# ST_LINK_V2_1.net
KiCad netlist of a schematic drawn in Altium Designer
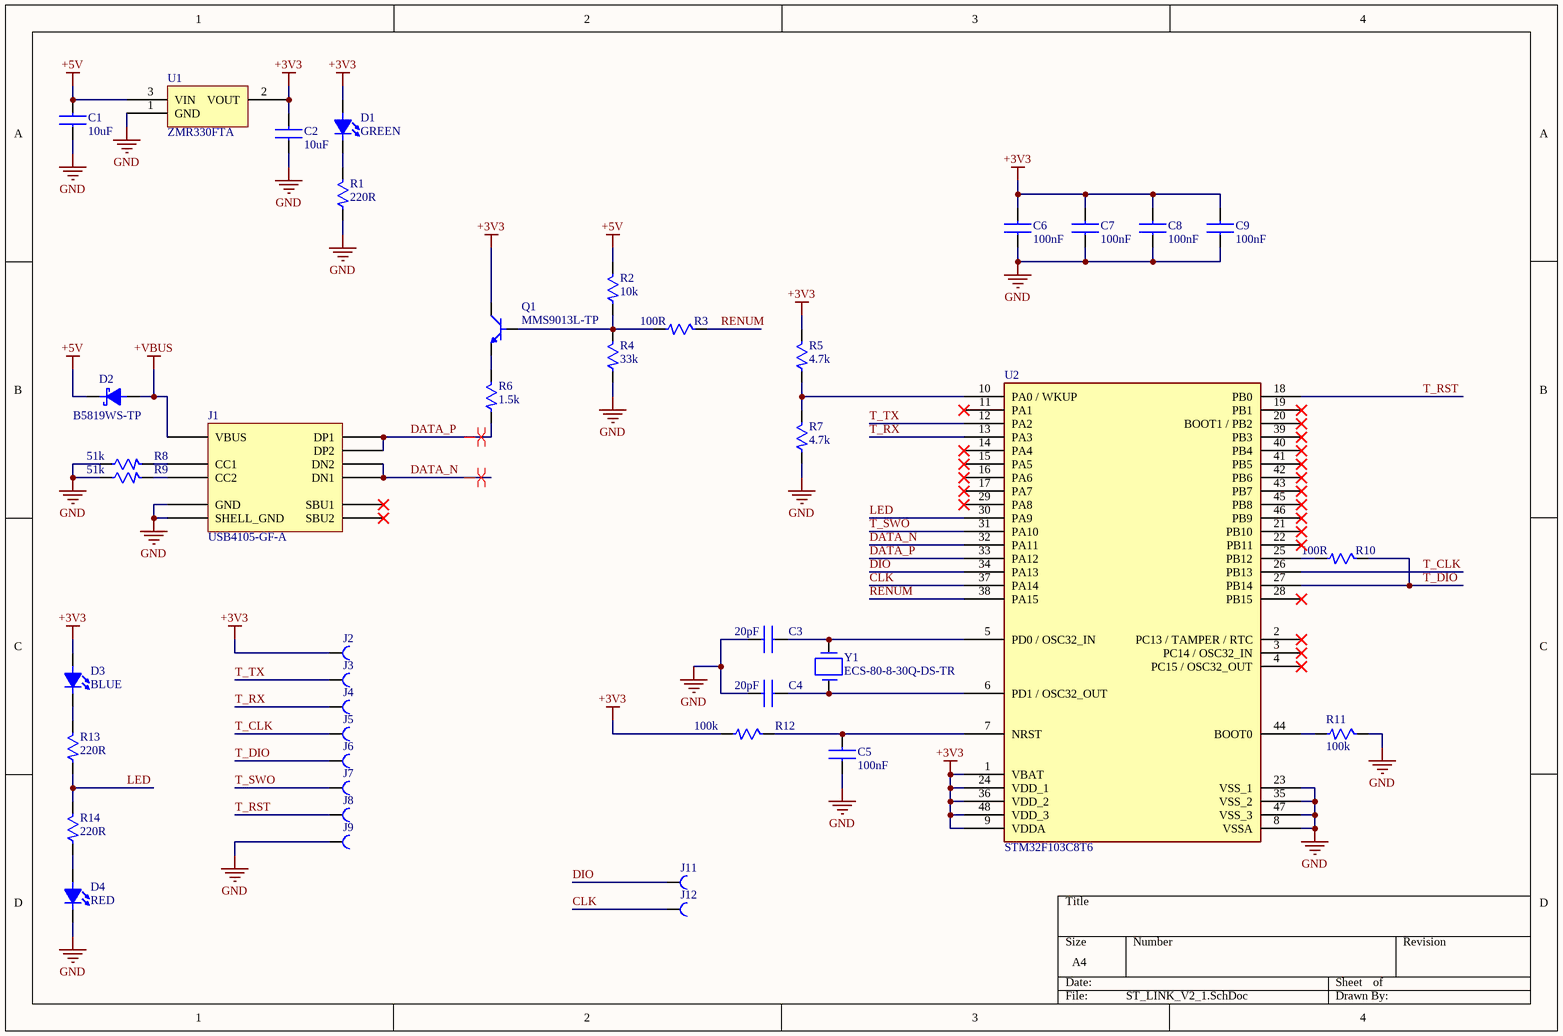
[diagram p0: ST_LINK_V2_1.SchDoc]

(export (version "E")
  (design (tool "Eeschema 10.0.6"))
  (components
    (comp (ref "C1")
      (value "10uF")
      (footprint "C_0603")
      (description "C Series 0603 10 uF 6.3 V ±10 % Tolerance X5R SMT Multilayer Ceramic Capacitor")
      (fields
        (field (name "MANUFACTURER") "TDK")
        (field (name "MANUFACTURER PART NUMBER") "C1608X5R0J106K080AB")
      )
      (libsource (lib "Altium_Library") (part "C1608X5R0J106K080AB"))
    )
    (comp (ref "C2")
      (value "10uF")
      (footprint "C_0603")
      (description "C Series 0603 10 uF 6.3 V ±10 % Tolerance X5R SMT Multilayer Ceramic Capacitor")
      (fields
        (field (name "MANUFACTURER") "TDK")
        (field (name "MANUFACTURER PART NUMBER") "C1608X5R0J106K080AB")
      )
      (libsource (lib "Altium_Library") (part "C1608X5R0J106K080AB"))
    )
    (comp (ref "C3")
      (value "20pF")
      (footprint "C_0603")
      (description "Cap Cer 0603 20PF 16V Ultra Stab")
      (fields
        (field (name "MANUFACTURER") "KEMET")
        (field (name "MANUFACTURER PART NUMBER") "C0603C200K4HACAUTO")
      )
      (libsource (lib "Altium_Library") (part "C0603C200K4HACAUTO"))
    )
    (comp (ref "C4")
      (value "20pF")
      (footprint "C_0603")
      (description "Cap Cer 0603 20PF 16V Ultra Stab")
      (fields
        (field (name "MANUFACTURER") "KEMET")
        (field (name "MANUFACTURER PART NUMBER") "C0603C200K4HACAUTO")
      )
      (libsource (lib "Altium_Library") (part "C0603C200K4HACAUTO"))
    )
    (comp (ref "C5")
      (value "100nF")
      (footprint "C_0603")
      (description "Cap Ceramic 0.1uF 16V X7R 20% SMD 0603 125 Paper T/R")
      (fields
        (field (name "MANUFACTURER") "KEMET")
        (field (name "MANUFACTURER PART NUMBER") "C0603C104M4RAC7411")
      )
      (libsource (lib "Altium_Library") (part "C0603C104M4RAC7411"))
    )
    (comp (ref "C6")
      (value "100nF")
      (footprint "C_0603")
      (description "Cap Ceramic 0.1uF 16V X7R 20% SMD 0603 125 Paper T/R")
      (fields
        (field (name "MANUFACTURER") "KEMET")
        (field (name "MANUFACTURER PART NUMBER") "C0603C104M4RAC7411")
      )
      (libsource (lib "Altium_Library") (part "C0603C104M4RAC7411"))
    )
    (comp (ref "C7")
      (value "100nF")
      (footprint "C_0603")
      (description "Cap Ceramic 0.1uF 16V X7R 20% SMD 0603 125 Paper T/R")
      (fields
        (field (name "MANUFACTURER") "KEMET")
        (field (name "MANUFACTURER PART NUMBER") "C0603C104M4RAC7411")
      )
      (libsource (lib "Altium_Library") (part "C0603C104M4RAC7411"))
    )
    (comp (ref "C8")
      (value "100nF")
      (footprint "C_0603")
      (description "Cap Ceramic 0.1uF 16V X7R 20% SMD 0603 125 Paper T/R")
      (fields
        (field (name "MANUFACTURER") "KEMET")
        (field (name "MANUFACTURER PART NUMBER") "C0603C104M4RAC7411")
      )
      (libsource (lib "Altium_Library") (part "C0603C104M4RAC7411"))
    )
    (comp (ref "C9")
      (value "100nF")
      (footprint "C_0603")
      (description "Cap Ceramic 0.1uF 16V X7R 20% SMD 0603 125 Paper T/R")
      (fields
        (field (name "MANUFACTURER") "KEMET")
        (field (name "MANUFACTURER PART NUMBER") "C0603C104M4RAC7411")
      )
      (libsource (lib "Altium_Library") (part "C0603C104M4RAC7411"))
    )
    (comp (ref "D1")
      (value "GREEN")
      (footprint "LED_0603_G")
      (description "Led, Green, 520 Nm, 3.2 V, 30 Ma, 430 Mcd Rohs Compliant: Yes")
      (fields
        (field (name "MANUFACTURER") "Wurth Electronics")
        (field (name "MANUFACTURER PART NUMBER") "150060GS75000")
      )
      (libsource (lib "Altium_Library") (part "150060GS75000"))
    )
    (comp (ref "D2")
      (value "B5819WS-TP")
      (footprint "SOD_323")
      (description "DIODE SCHOTTKY 40V 1A SOD323")
      (fields (field (name "MANUFACTURER") "MCC"))
      (libsource (lib "Altium_Library") (part "B5819WS-TP"))
    )
    (comp (ref "D3")
      (value "BLUE")
      (footprint "LED_0603_B")
      (description "SMT Mono-color Chip Led Watercle")
      (fields
        (field (name "MANUFACTURER") "Wurth Electronics")
        (field (name "MANUFACTURER PART NUMBER") "150060BS75003")
      )
      (libsource (lib "Altium_Library") (part "150060BS75003"))
    )
    (comp (ref "D4")
      (value "RED")
      (footprint "LED_0603_R")
      (description "LED Low-Power Uni-Color Red 630nm 2V 2-Pin Chip 0603(1608Metric) T/R")
      (fields
        (field (name "MANUFACTURER") "Wurth Electronics")
        (field (name "MANUFACTURER PART NUMBER") "150060RS75000")
      )
      (libsource (lib "Altium_Library") (part "150060RS75000"))
    )
    (comp (ref "J1")
      (value "USB4105-GF-A")
      (footprint "USB4105-GF-A")
      (description "Conn USB 2.0 Type C RCP 24 POS 0.3mm/0.5mm Solder RA SMD 24 Terminal 1 Port T/R")
      (fields (field (name "MANUFACTURER") "Global Connector Technology"))
      (libsource (lib "Altium_Library") (part "USB4105-GF-A"))
    )
    (comp (ref "J2")
      (value "CONST_PAD")
      (footprint "CONST_PAD")
      (libsource (lib "Altium_Library") (part "CONST_PAD"))
    )
    (comp (ref "J3")
      (value "CONST_PAD")
      (footprint "CONST_PAD")
      (libsource (lib "Altium_Library") (part "CONST_PAD"))
    )
    (comp (ref "J4")
      (value "CONST_PAD")
      (footprint "CONST_PAD")
      (libsource (lib "Altium_Library") (part "CONST_PAD"))
    )
    (comp (ref "J5")
      (value "CONST_PAD")
      (footprint "CONST_PAD")
      (libsource (lib "Altium_Library") (part "CONST_PAD"))
    )
    (comp (ref "J6")
      (value "CONST_PAD")
      (footprint "CONST_PAD")
      (libsource (lib "Altium_Library") (part "CONST_PAD"))
    )
    (comp (ref "J7")
      (value "CONST_PAD")
      (footprint "CONST_PAD")
      (libsource (lib "Altium_Library") (part "CONST_PAD"))
    )
    (comp (ref "J8")
      (value "CONST_PAD")
      (footprint "CONST_PAD")
      (libsource (lib "Altium_Library") (part "CONST_PAD"))
    )
    (comp (ref "J9")
      (value "CONST_PAD")
      (footprint "CONST_PAD")
      (libsource (lib "Altium_Library") (part "CONST_PAD"))
    )
    (comp (ref "J11")
      (value "CONST_PAD")
      (footprint "CONST_PAD")
      (libsource (lib "Altium_Library") (part "CONST_PAD"))
    )
    (comp (ref "J12")
      (value "CONST_PAD")
      (footprint "CONST_PAD")
      (libsource (lib "Altium_Library") (part "CONST_PAD"))
    )
    (comp (ref "Q1")
      (value "MMS9013L-TP")
      (footprint "SOT_23")
      (description "Trans Gp Bjt NPN 25V 0.5A 3-PIN SOT-23 T/r")
      (fields (field (name "MANUFACTURER") "MCC"))
      (libsource (lib "Altium_Library") (part "MMS9013L-TP"))
    )
    (comp (ref "R1")
      (value "220R")
      (footprint "R_0603")
      (description "Res Thick Film 0603 220 Ohm 1% 0.1W(1/10W) ±100ppm/°C Pad SMD T/R")
      (fields
        (field (name "MANUFACTURER") "Yageo")
        (field (name "MANUFACTURER PART NUMBER") "RC0603FR-07220RL")
      )
      (libsource (lib "Altium_Library") (part "RC0603FR-07220RL"))
    )
    (comp (ref "R2")
      (value "10k")
      (footprint "R_0603")
      (description "RES SMD 10K OHM 1% 1/10W 0603")
      (fields
        (field (name "MANUFACTURER") "Yageo")
        (field (name "MANUFACTURER PART NUMBER") "RC0603FR-0710KL")
      )
      (libsource (lib "Altium_Library") (part "RC0603FR-0710KL"))
    )
    (comp (ref "R3")
      (value "100R")
      (footprint "R_0603")
      (description "Res Thick Film 0603 100 Ohm 1% 1/10W ±100ppm/°C Molded SMD SMD Paper T/R")
      (fields
        (field (name "MANUFACTURER") "Yageo")
        (field (name "MANUFACTURER PART NUMBER") "AR0603FR-07100RL")
      )
      (libsource (lib "Altium_Library") (part "AR0603FR-07100RL"))
    )
    (comp (ref "R4")
      (value "33k")
      (footprint "R_0603")
      (description "Res Thick Film 0603 33K Ohm 1% 0.1W(1/10W) ±100ppm/C Pad SMD T/R")
      (fields
        (field (name "MANUFACTURER") "Yageo")
        (field (name "MANUFACTURER PART NUMBER") "RC0603FR-0733KL")
      )
      (libsource (lib "Altium_Library") (part "RC0603FR-0733KL"))
    )
    (comp (ref "R5")
      (value "4.7k")
      (footprint "R_0603")
      (description "Res Thick Film 0603 4.7K Ohm 1% 0.1W(1/10W) ±100ppm/C Pad SMD T/R")
      (fields
        (field (name "MANUFACTURER") "TE Connectivity")
        (field (name "MANUFACTURER PART NUMBER") "1622960-1")
      )
      (libsource (lib "Altium_Library") (part "1622960-1"))
    )
    (comp (ref "R6")
      (value "1.5k")
      (footprint "R_0603")
      (description "Res General Purpose Thick Film 0603 1.5K Ohm 1% 1/10W ±100ppm/°C Molded SMD Paper T/R")
      (fields
        (field (name "MANUFACTURER") "Yageo")
        (field (name "MANUFACTURER PART NUMBER") "RC0603FR-071K5L")
      )
      (libsource (lib "Altium_Library") (part "RC0603FR-071K5L"))
    )
    (comp (ref "R7")
      (value "4.7k")
      (footprint "R_0603")
      (description "Res Thick Film 0603 4.7K Ohm 1% 0.1W(1/10W) ±100ppm/C Pad SMD T/R")
      (fields
        (field (name "MANUFACTURER") "TE Connectivity")
        (field (name "MANUFACTURER PART NUMBER") "1622960-1")
      )
      (libsource (lib "Altium_Library") (part "1622960-1"))
    )
    (comp (ref "R8")
      (value "51k")
      (footprint "R_0603")
      (description "Res Thick Film 0603 51K Ohm 1% 1/10W ±100ppm/°C Molded SMD Paper T/R")
      (fields
        (field (name "MANUFACTURER") "Yageo")
        (field (name "MANUFACTURER PART NUMBER") "AF0603FR-0751KL")
      )
      (libsource (lib "Altium_Library") (part "AF0603FR-0751KL"))
    )
    (comp (ref "R9")
      (value "51k")
      (footprint "R_0603")
      (description "Res Thick Film 0603 51K Ohm 1% 1/10W ±100ppm/°C Molded SMD Paper T/R")
      (fields
        (field (name "MANUFACTURER") "Yageo")
        (field (name "MANUFACTURER PART NUMBER") "AF0603FR-0751KL")
      )
      (libsource (lib "Altium_Library") (part "AF0603FR-0751KL"))
    )
    (comp (ref "R10")
      (value "100R")
      (footprint "R_0603")
      (description "Res Thick Film 0603 100 Ohm 1% 1/10W ±100ppm/°C Molded SMD SMD Paper T/R")
      (fields
        (field (name "MANUFACTURER") "Yageo")
        (field (name "MANUFACTURER PART NUMBER") "AR0603FR-07100RL")
      )
      (libsource (lib "Altium_Library") (part "AR0603FR-07100RL"))
    )
    (comp (ref "R11")
      (value "100k")
      (footprint "R_0603")
      (description "RES SMD 100K OHM 1% 1/10W 0603")
      (fields
        (field (name "MANUFACTURER") "Yageo")
        (field (name "MANUFACTURER PART NUMBER") "RC0603FR-07100KL")
      )
      (libsource (lib "Altium_Library") (part "RC0603FR-07100KL"))
    )
    (comp (ref "R12")
      (value "100k")
      (footprint "R_0603")
      (description "RES SMD 100K OHM 1% 1/10W 0603")
      (fields
        (field (name "MANUFACTURER") "Yageo")
        (field (name "MANUFACTURER PART NUMBER") "RC0603FR-07100KL")
      )
      (libsource (lib "Altium_Library") (part "RC0603FR-07100KL"))
    )
    (comp (ref "R13")
      (value "220R")
      (footprint "R_0603")
      (description "Res Thick Film 0603 220 Ohm 1% 0.1W(1/10W) ±100ppm/°C Pad SMD T/R")
      (fields
        (field (name "MANUFACTURER") "Yageo")
        (field (name "MANUFACTURER PART NUMBER") "RC0603FR-07220RL")
      )
      (libsource (lib "Altium_Library") (part "RC0603FR-07220RL"))
    )
    (comp (ref "R14")
      (value "220R")
      (footprint "R_0603")
      (description "Res Thick Film 0603 220 Ohm 1% 0.1W(1/10W) ±100ppm/°C Pad SMD T/R")
      (fields
        (field (name "MANUFACTURER") "Yageo")
        (field (name "MANUFACTURER PART NUMBER") "RC0603FR-07220RL")
      )
      (libsource (lib "Altium_Library") (part "RC0603FR-07220RL"))
    )
    (comp (ref "U1")
      (value "ZMR330FTA")
      (footprint "SOT_23_REG")
      (description "ZMR330 Series 3.3 V 50 mA Fixed Output SMT Miniature Voltage Regulator - SOT-23")
      (fields (field (name "MANUFACTURER") "Diodes Zetex"))
      (libsource (lib "Altium_Library") (part "ZMR330FTA"))
    )
    (comp (ref "U2")
      (value "STM32F103C8T6")
      (footprint "LQFP48")
      (description "IC MCU 32BIT 64KB FLASH 48LQFP")
      (fields (field (name "MANUFACTURER") "STMicroelectronics"))
      (libsource (lib "Altium_Library") (part "STM32F103C8T6"))
    )
    (comp (ref "Y1")
      (value "ECS-80-8-30Q-DS-TR")
      (footprint "ECS-80-8-30Q-DS-TR")
      (description "Crystal 8.000 Mhz 8PF SMD")
      (fields (field (name "MANUFACTURER") "ECS International"))
      (libsource (lib "Altium_Library") (part "ECS-80-8-30Q-DS-TR"))
    )
  )
  (nets
    (net (code "1") (name "+3V3") (class "Default")
      (node (ref "C2") (pin "2") (pinfunction "2_2") (pintype "passive"))
      (node (ref "C6") (pin "2") (pinfunction "2_2") (pintype "passive"))
      (node (ref "C7") (pin "2") (pinfunction "2_2") (pintype "passive"))
      (node (ref "C8") (pin "2") (pinfunction "2_2") (pintype "passive"))
      (node (ref "C9") (pin "2") (pinfunction "2_2") (pintype "passive"))
      (node (ref "D1") (pin "2") (pinfunction "anode_2") (pintype "passive"))
      (node (ref "D3") (pin "2") (pinfunction "anode_2") (pintype "passive"))
      (node (ref "J2") (pin "0") (pinfunction "PAD_0") (pintype "passive"))
      (node (ref "Q1") (pin "3") (pinfunction "3_3") (pintype "passive"))
      (node (ref "R12") (pin "1") (pinfunction "1_1") (pintype "passive"))
      (node (ref "R5") (pin "2") (pinfunction "2_2") (pintype "passive"))
      (node (ref "U1") (pin "2") (pinfunction "VOUT_2") (pintype "passive"))
      (node (ref "U2") (pin "1") (pinfunction "VBAT_1") (pintype "passive"))
      (node (ref "U2") (pin "24") (pinfunction "VDD_1_24") (pintype "passive"))
      (node (ref "U2") (pin "36") (pinfunction "VDD_2_36") (pintype "passive"))
      (node (ref "U2") (pin "48") (pinfunction "VDD_3_48") (pintype "passive"))
      (node (ref "U2") (pin "9") (pinfunction "VDDA_9") (pintype "passive"))
    )
    (net (code "2") (name "+5V") (class "Default")
      (node (ref "C1") (pin "2") (pinfunction "2_2") (pintype "passive"))
      (node (ref "D2") (pin "1") (pinfunction "cathode_1") (pintype "passive"))
      (node (ref "R2") (pin "2") (pinfunction "2_2") (pintype "passive"))
      (node (ref "U1") (pin "3") (pinfunction "VIN_3") (pintype "passive"))
    )
    (net (code "3") (name "+VBUS") (class "Default")
      (node (ref "D2") (pin "2") (pinfunction "anode_2") (pintype "passive"))
      (node (ref "J1") (pin "VBUS") (pinfunction "VBUS_VBUS") (pintype "passive"))
    )
    (net (code "4") (name "/CLK") (class "Default")
      (node (ref "J12") (pin "0") (pinfunction "PAD_0") (pintype "passive"))
      (node (ref "U2") (pin "37") (pinfunction "PA14_37") (pintype "passive"))
    )
    (net (code "5") (name "/DATA_N") (class "Default")
      (node (ref "J1") (pin "DN1") (pinfunction "DN1_DN1") (pintype "passive"))
      (node (ref "J1") (pin "DN2") (pinfunction "DN2_DN2") (pintype "passive"))
      (node (ref "U2") (pin "32") (pinfunction "PA11_32") (pintype "passive"))
    )
    (net (code "6") (name "/DATA_P") (class "Default")
      (node (ref "J1") (pin "DP1") (pinfunction "DP1_DP1") (pintype "passive"))
      (node (ref "J1") (pin "DP2") (pinfunction "DP2_DP2") (pintype "passive"))
      (node (ref "R6") (pin "1") (pinfunction "1_1") (pintype "passive"))
      (node (ref "U2") (pin "33") (pinfunction "PA12_33") (pintype "passive"))
    )
    (net (code "7") (name "/DIO") (class "Default")
      (node (ref "J11") (pin "0") (pinfunction "PAD_0") (pintype "passive"))
      (node (ref "U2") (pin "34") (pinfunction "PA13_34") (pintype "passive"))
    )
    (net (code "8") (name "/LED") (class "Default")
      (node (ref "R13") (pin "1") (pinfunction "1_1") (pintype "passive"))
      (node (ref "R14") (pin "2") (pinfunction "2_2") (pintype "passive"))
      (node (ref "U2") (pin "30") (pinfunction "PA9_30") (pintype "passive"))
    )
    (net (code "9") (name "/RENUM") (class "Default")
      (node (ref "R3") (pin "2") (pinfunction "2_2") (pintype "passive"))
      (node (ref "U2") (pin "38") (pinfunction "PA15_38") (pintype "passive"))
    )
    (net (code "10") (name "/T_CLK") (class "Default")
      (node (ref "J5") (pin "0") (pinfunction "PAD_0") (pintype "passive"))
      (node (ref "U2") (pin "26") (pinfunction "PB13_26") (pintype "passive"))
    )
    (net (code "11") (name "/T_DIO") (class "Default")
      (node (ref "J6") (pin "0") (pinfunction "PAD_0") (pintype "passive"))
      (node (ref "R10") (pin "2") (pinfunction "2_2") (pintype "passive"))
      (node (ref "U2") (pin "27") (pinfunction "PB14_27") (pintype "passive"))
    )
    (net (code "12") (name "/T_RST") (class "Default")
      (node (ref "J8") (pin "0") (pinfunction "PAD_0") (pintype "passive"))
      (node (ref "U2") (pin "18") (pinfunction "PB0_18") (pintype "passive"))
    )
    (net (code "13") (name "/T_RX") (class "Default")
      (node (ref "J4") (pin "0") (pinfunction "PAD_0") (pintype "passive"))
      (node (ref "U2") (pin "13") (pinfunction "PA3_13") (pintype "passive"))
    )
    (net (code "14") (name "/T_SWO") (class "Default")
      (node (ref "J7") (pin "0") (pinfunction "PAD_0") (pintype "passive"))
      (node (ref "U2") (pin "31") (pinfunction "PA10_31") (pintype "passive"))
    )
    (net (code "15") (name "/T_TX") (class "Default")
      (node (ref "J3") (pin "0") (pinfunction "PAD_0") (pintype "passive"))
      (node (ref "U2") (pin "12") (pinfunction "PA2_12") (pintype "passive"))
    )
    (net (code "16") (name "GND") (class "Default")
      (node (ref "C1") (pin "1") (pinfunction "1_1") (pintype "passive"))
      (node (ref "C2") (pin "1") (pinfunction "1_1") (pintype "passive"))
      (node (ref "C3") (pin "1") (pinfunction "1_1") (pintype "passive"))
      (node (ref "C4") (pin "1") (pinfunction "1_1") (pintype "passive"))
      (node (ref "C5") (pin "1") (pinfunction "1_1") (pintype "passive"))
      (node (ref "C6") (pin "1") (pinfunction "1_1") (pintype "passive"))
      (node (ref "C7") (pin "1") (pinfunction "1_1") (pintype "passive"))
      (node (ref "C8") (pin "1") (pinfunction "1_1") (pintype "passive"))
      (node (ref "C9") (pin "1") (pinfunction "1_1") (pintype "passive"))
      (node (ref "D4") (pin "1") (pinfunction "cathode_1") (pintype "passive"))
      (node (ref "J1") (pin "GND") (pinfunction "GND_GND") (pintype "passive"))
      (node (ref "J1") (pin "SHELL_GND") (pinfunction "SHELL_GND_SHELL_GND") (pintype "passive"))
      (node (ref "J9") (pin "0") (pinfunction "PAD_0") (pintype "passive"))
      (node (ref "R1") (pin "1") (pinfunction "1_1") (pintype "passive"))
      (node (ref "R11") (pin "2") (pinfunction "2_2") (pintype "passive"))
      (node (ref "R4") (pin "1") (pinfunction "1_1") (pintype "passive"))
      (node (ref "R7") (pin "1") (pinfunction "1_1") (pintype "passive"))
      (node (ref "R8") (pin "2") (pinfunction "2_2") (pintype "passive"))
      (node (ref "R9") (pin "2") (pinfunction "2_2") (pintype "passive"))
      (node (ref "U1") (pin "1") (pinfunction "GND_1") (pintype "passive"))
      (node (ref "U2") (pin "23") (pinfunction "VSS_1_23") (pintype "passive"))
      (node (ref "U2") (pin "35") (pinfunction "VSS_2_35") (pintype "passive"))
      (node (ref "U2") (pin "47") (pinfunction "VSS_3_47") (pintype "passive"))
      (node (ref "U2") (pin "8") (pinfunction "VSSA_8") (pintype "passive"))
    )
    (net (code "17") (name "Net-(D1-cathode)") (class "Default")
      (node (ref "D1") (pin "1") (pinfunction "cathode_1") (pintype "passive"))
      (node (ref "R1") (pin "2") (pinfunction "2_2") (pintype "passive"))
    )
    (net (code "18") (name "Net-(D3-cathode)") (class "Default")
      (node (ref "D3") (pin "1") (pinfunction "cathode_1") (pintype "passive"))
      (node (ref "R13") (pin "2") (pinfunction "2_2") (pintype "passive"))
    )
    (net (code "19") (name "Net-(D4-anode)") (class "Default")
      (node (ref "D4") (pin "2") (pinfunction "anode_2") (pintype "passive"))
      (node (ref "R14") (pin "1") (pinfunction "1_1") (pintype "passive"))
    )
    (net (code "20") (name "Net-(J1-PadCC1)") (class "Default")
      (node (ref "J1") (pin "CC1") (pinfunction "CC1_CC1") (pintype "passive"))
      (node (ref "R8") (pin "1") (pinfunction "1_1") (pintype "passive"))
    )
    (net (code "21") (name "Net-(J1-PadCC2)") (class "Default")
      (node (ref "J1") (pin "CC2") (pinfunction "CC2_CC2") (pintype "passive"))
      (node (ref "R9") (pin "1") (pinfunction "1_1") (pintype "passive"))
    )
    (net (code "22") (name "Net-(Q1-Pad1)") (class "Default")
      (node (ref "Q1") (pin "1") (pinfunction "1_1") (pintype "passive"))
      (node (ref "R2") (pin "1") (pinfunction "1_1") (pintype "passive"))
      (node (ref "R3") (pin "1") (pinfunction "1_1") (pintype "passive"))
      (node (ref "R4") (pin "2") (pinfunction "2_2") (pintype "passive"))
    )
    (net (code "23") (name "Net-(Q1-Pad2)") (class "Default")
      (node (ref "Q1") (pin "2") (pinfunction "2_2") (pintype "passive"))
      (node (ref "R6") (pin "2") (pinfunction "2_2") (pintype "passive"))
    )
    (net (code "24") (name "Net-(U2-BOOT0)") (class "Default")
      (node (ref "R11") (pin "1") (pinfunction "1_1") (pintype "passive"))
      (node (ref "U2") (pin "44") (pinfunction "BOOT0_44") (pintype "passive"))
    )
    (net (code "25") (name "Net-(U2-NRST)") (class "Default")
      (node (ref "C5") (pin "2") (pinfunction "2_2") (pintype "passive"))
      (node (ref "R12") (pin "2") (pinfunction "2_2") (pintype "passive"))
      (node (ref "U2") (pin "7") (pinfunction "NRST_7") (pintype "passive"))
    )
    (net (code "26") (name "Net-(U2-PA0_{slash}_WKUP)") (class "Default")
      (node (ref "R5") (pin "1") (pinfunction "1_1") (pintype "passive"))
      (node (ref "R7") (pin "2") (pinfunction "2_2") (pintype "passive"))
      (node (ref "U2") (pin "10") (pinfunction "PA0_/_WKUP_10") (pintype "passive"))
    )
    (net (code "27") (name "Net-(U2-PB12)") (class "Default")
      (node (ref "R10") (pin "1") (pinfunction "1_1") (pintype "passive"))
      (node (ref "U2") (pin "25") (pinfunction "PB12_25") (pintype "passive"))
    )
    (net (code "28") (name "Net-(U2-PD0_{slash}_OSC32_IN)") (class "Default")
      (node (ref "C3") (pin "2") (pinfunction "2_2") (pintype "passive"))
      (node (ref "U2") (pin "5") (pinfunction "PD0_/_OSC32_IN_5") (pintype "passive"))
      (node (ref "Y1") (pin "2") (pinfunction "2_2") (pintype "passive"))
    )
    (net (code "29") (name "Net-(U2-PD1_{slash}_OSC32_OUT)") (class "Default")
      (node (ref "C4") (pin "2") (pinfunction "2_2") (pintype "passive"))
      (node (ref "U2") (pin "6") (pinfunction "PD1_/_OSC32_OUT_6") (pintype "passive"))
      (node (ref "Y1") (pin "1") (pinfunction "1_1") (pintype "passive"))
    )
    (net (code "30") (name "unconnected-(J1-PadSBU1)") (class "Default")
      (node (ref "J1") (pin "SBU1") (pinfunction "SBU1_SBU1") (pintype "passive+no_connect"))
    )
    (net (code "31") (name "unconnected-(J1-PadSBU2)") (class "Default")
      (node (ref "J1") (pin "SBU2") (pinfunction "SBU2_SBU2") (pintype "passive+no_connect"))
    )
    (net (code "32") (name "unconnected-(U2-BOOT1_{slash}_PB2-Pad20)") (class "Default")
      (node (ref "U2") (pin "20") (pinfunction "BOOT1_/_PB2_20") (pintype "passive+no_connect"))
    )
    (net (code "33") (name "unconnected-(U2-PA1-Pad11)") (class "Default")
      (node (ref "U2") (pin "11") (pinfunction "PA1_11") (pintype "passive+no_connect"))
    )
    (net (code "34") (name "unconnected-(U2-PA4-Pad14)") (class "Default")
      (node (ref "U2") (pin "14") (pinfunction "PA4_14") (pintype "passive+no_connect"))
    )
    (net (code "35") (name "unconnected-(U2-PA5-Pad15)") (class "Default")
      (node (ref "U2") (pin "15") (pinfunction "PA5_15") (pintype "passive+no_connect"))
    )
    (net (code "36") (name "unconnected-(U2-PA6-Pad16)") (class "Default")
      (node (ref "U2") (pin "16") (pinfunction "PA6_16") (pintype "passive+no_connect"))
    )
    (net (code "37") (name "unconnected-(U2-PA7-Pad17)") (class "Default")
      (node (ref "U2") (pin "17") (pinfunction "PA7_17") (pintype "passive+no_connect"))
    )
    (net (code "38") (name "unconnected-(U2-PA8-Pad29)") (class "Default")
      (node (ref "U2") (pin "29") (pinfunction "PA8_29") (pintype "passive+no_connect"))
    )
    (net (code "39") (name "unconnected-(U2-PB1-Pad19)") (class "Default")
      (node (ref "U2") (pin "19") (pinfunction "PB1_19") (pintype "passive+no_connect"))
    )
    (net (code "40") (name "unconnected-(U2-PB3-Pad39)") (class "Default")
      (node (ref "U2") (pin "39") (pinfunction "PB3_39") (pintype "passive+no_connect"))
    )
    (net (code "41") (name "unconnected-(U2-PB4-Pad40)") (class "Default")
      (node (ref "U2") (pin "40") (pinfunction "PB4_40") (pintype "passive+no_connect"))
    )
    (net (code "42") (name "unconnected-(U2-PB5-Pad41)") (class "Default")
      (node (ref "U2") (pin "41") (pinfunction "PB5_41") (pintype "passive+no_connect"))
    )
    (net (code "43") (name "unconnected-(U2-PB6-Pad42)") (class "Default")
      (node (ref "U2") (pin "42") (pinfunction "PB6_42") (pintype "passive+no_connect"))
    )
    (net (code "44") (name "unconnected-(U2-PB7-Pad43)") (class "Default")
      (node (ref "U2") (pin "43") (pinfunction "PB7_43") (pintype "passive+no_connect"))
    )
    (net (code "45") (name "unconnected-(U2-PB8-Pad45)") (class "Default")
      (node (ref "U2") (pin "45") (pinfunction "PB8_45") (pintype "passive+no_connect"))
    )
    (net (code "46") (name "unconnected-(U2-PB9-Pad46)") (class "Default")
      (node (ref "U2") (pin "46") (pinfunction "PB9_46") (pintype "passive+no_connect"))
    )
    (net (code "47") (name "unconnected-(U2-PB10-Pad21)") (class "Default")
      (node (ref "U2") (pin "21") (pinfunction "PB10_21") (pintype "passive+no_connect"))
    )
    (net (code "48") (name "unconnected-(U2-PB11-Pad22)") (class "Default")
      (node (ref "U2") (pin "22") (pinfunction "PB11_22") (pintype "passive+no_connect"))
    )
    (net (code "49") (name "unconnected-(U2-PB15-Pad28)") (class "Default")
      (node (ref "U2") (pin "28") (pinfunction "PB15_28") (pintype "passive+no_connect"))
    )
    (net (code "50") (name "unconnected-(U2-PC13_{slash}_TAMPER_{slash}_RTC-Pad2)") (class "Default")
      (node (ref "U2") (pin "2") (pinfunction "PC13_/_TAMPER_/_RTC_2") (pintype "passive+no_connect"))
    )
    (net (code "51") (name "unconnected-(U2-PC14_{slash}_OSC32_IN-Pad3)") (class "Default")
      (node (ref "U2") (pin "3") (pinfunction "PC14_/_OSC32_IN_3") (pintype "passive+no_connect"))
    )
    (net (code "52") (name "unconnected-(U2-PC15_{slash}_OSC32_OUT-Pad4)") (class "Default")
      (node (ref "U2") (pin "4") (pinfunction "PC15_/_OSC32_OUT_4") (pintype "passive+no_connect"))
    )
  )
)
